# 2017-09-15_drum_circuits.net
KiCad netlist of a schematic drawn in EAGLE
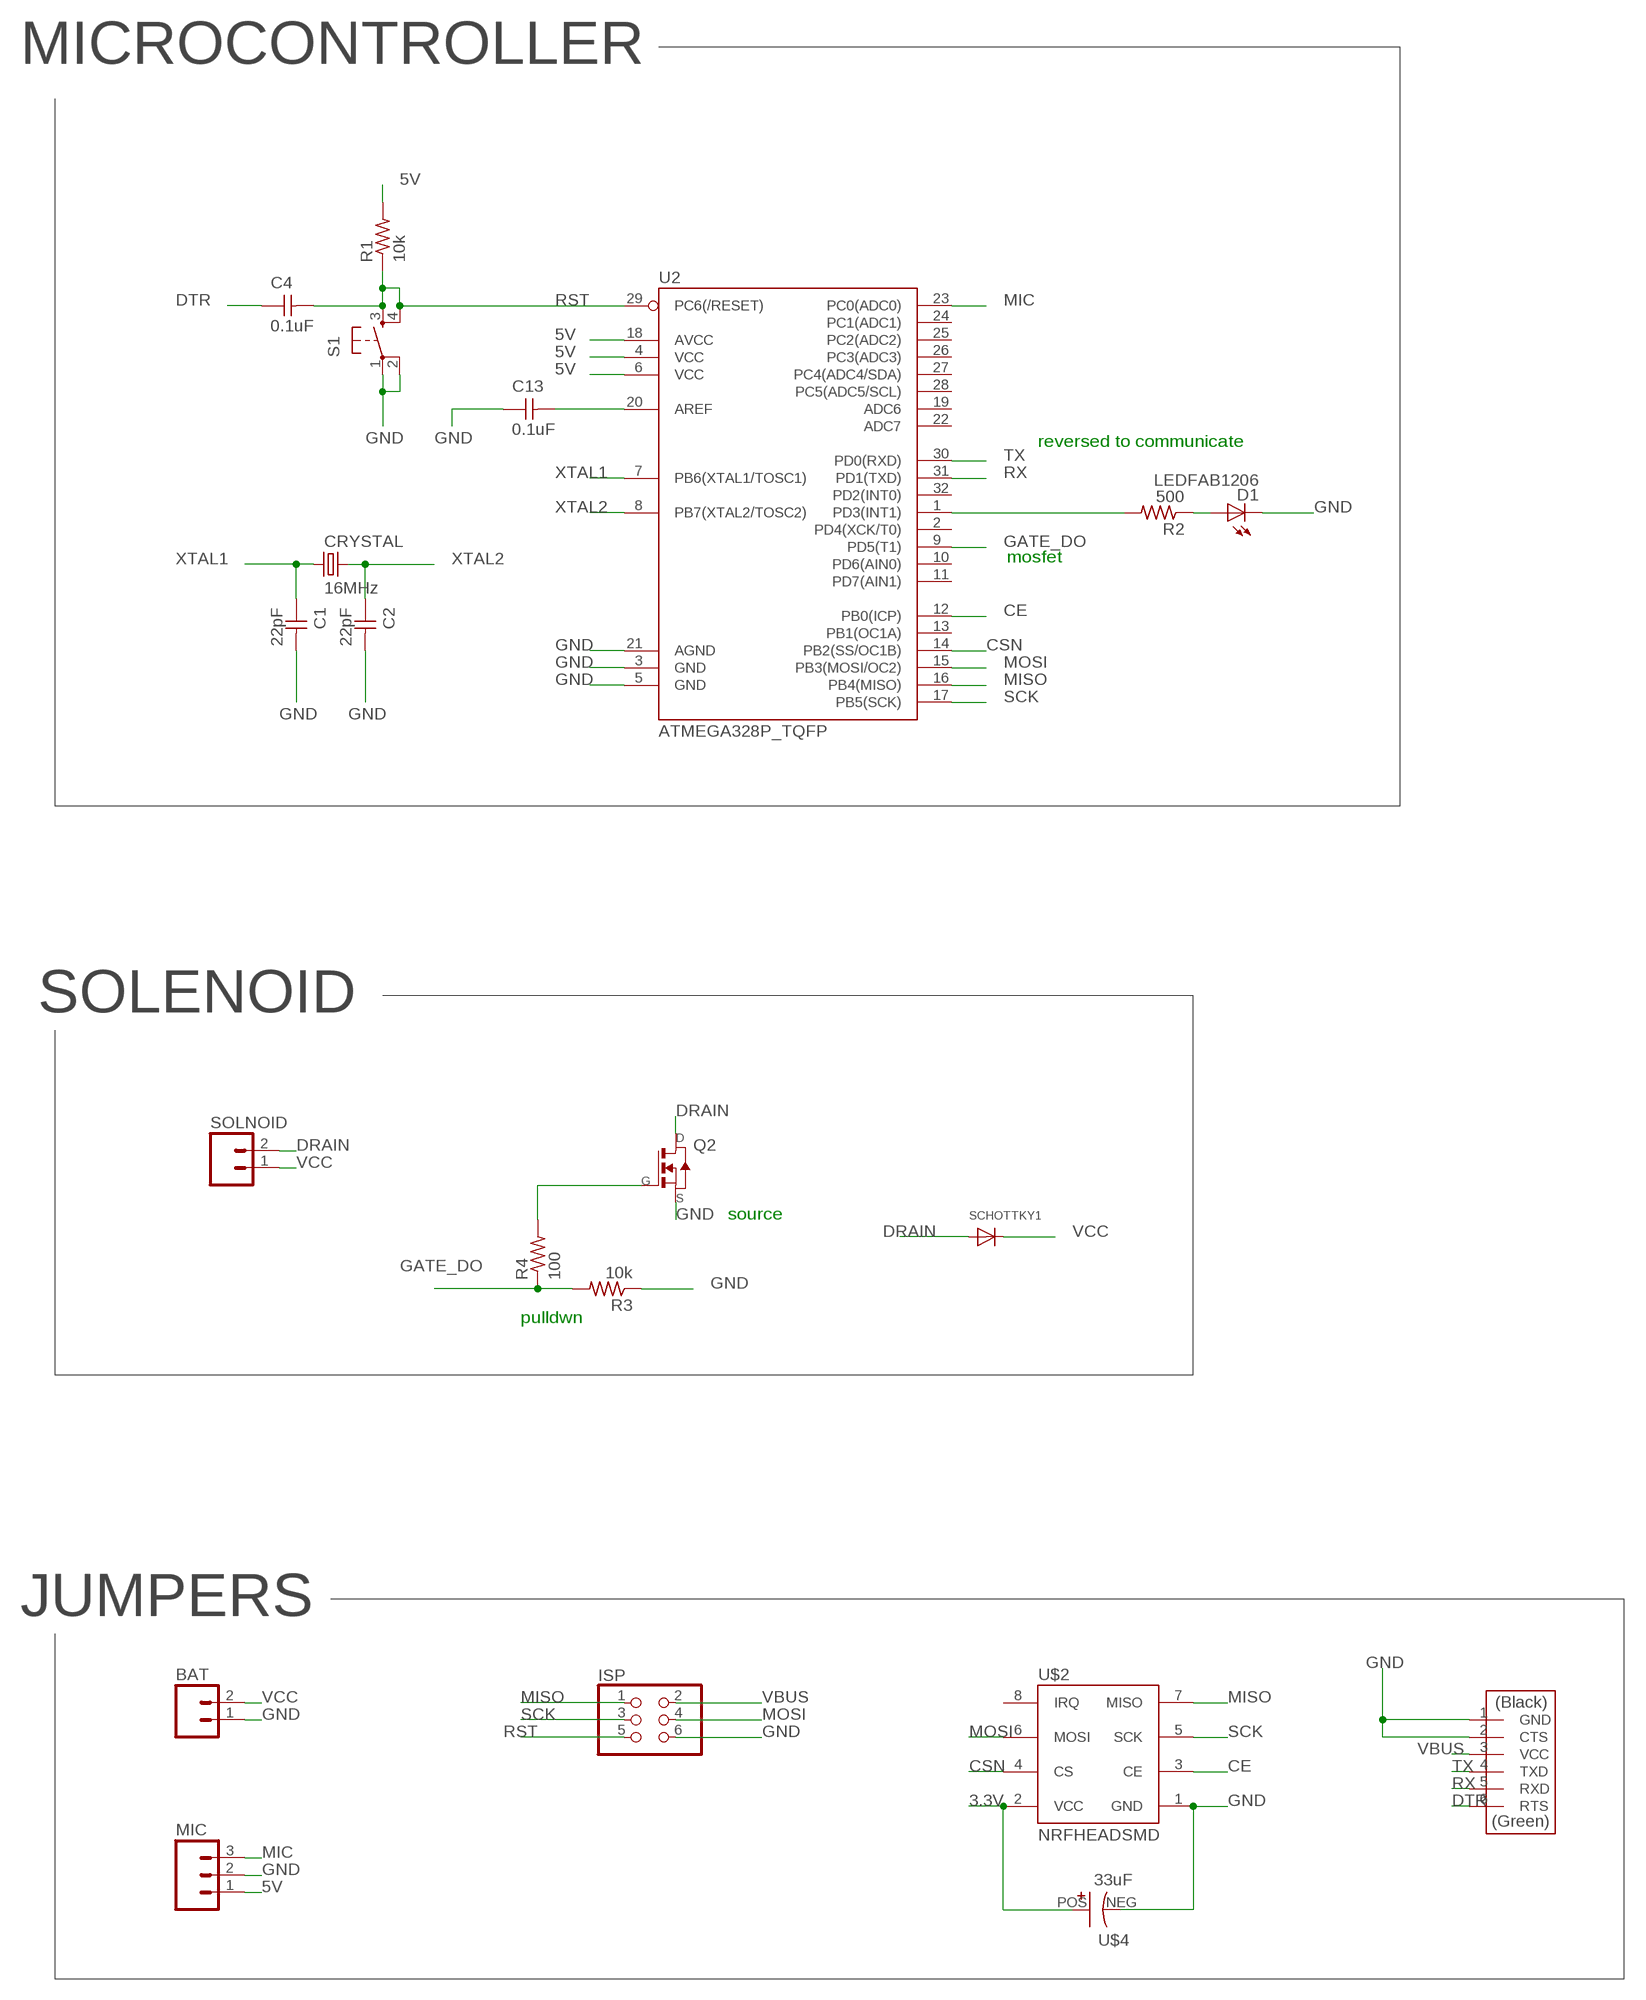
[diagram p0: schematic, sheet 1, part 1 of 2]
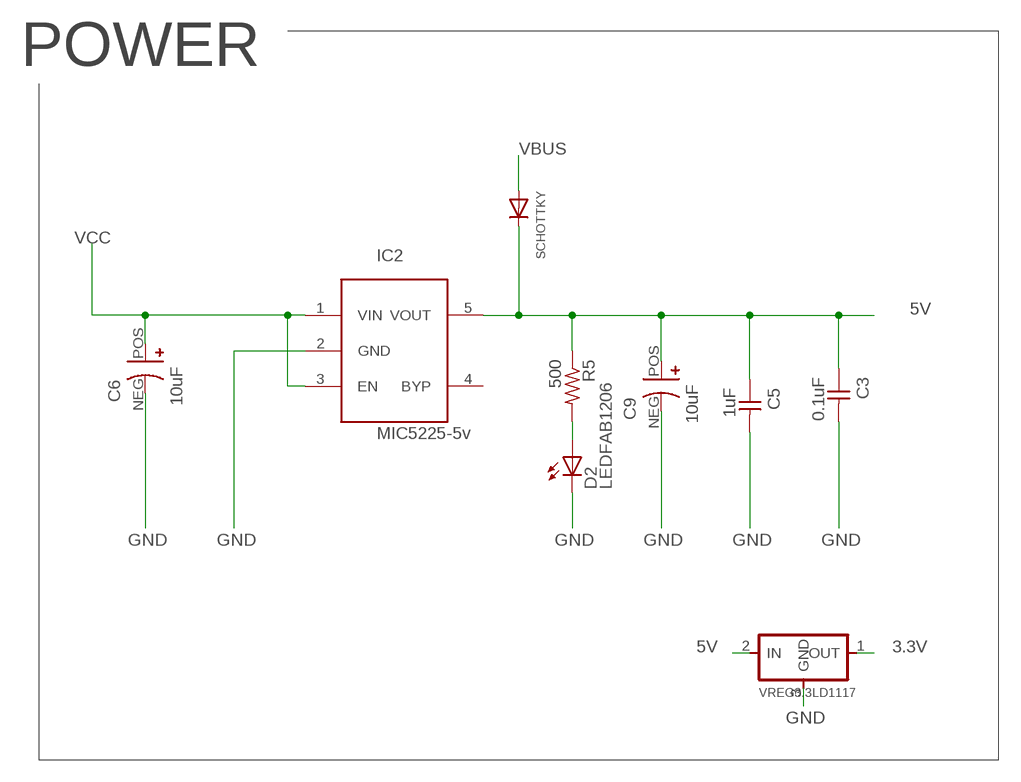
[diagram p1: schematic, sheet 1, part 2 of 2]

(export (version "E")
  (design (tool "Eeschema 10.0.6"))
  (components
    (comp (ref "BAT")
      (value "M02PTH")
      (footprint "eagle-import:1X02")
      (libsource (lib "eagle-import") (part "M02PTH"))
    )
    (comp (ref "C1")
      (value "22pF")
      (footprint "eagle-import:C1206FAB")
      (libsource (lib "eagle-import") (part "CAP-UNPOLARIZEDFAB"))
    )
    (comp (ref "C2")
      (value "22pF")
      (footprint "eagle-import:C1206FAB")
      (libsource (lib "eagle-import") (part "CAP-UNPOLARIZEDFAB"))
    )
    (comp (ref "C3")
      (value "0.1uF")
      (footprint "eagle-import:C1206FAB")
      (libsource (lib "eagle-import") (part "CAP-UNPOLARIZEDFAB"))
    )
    (comp (ref "C4")
      (value "0.1uF")
      (footprint "eagle-import:C1206FAB")
      (libsource (lib "eagle-import") (part "CAP-UNPOLARIZEDFAB"))
    )
    (comp (ref "C5")
      (value "1uF")
      (footprint "eagle-import:C1206FAB")
      (libsource (lib "eagle-import") (part "CAP-UNPOLARIZEDFAB"))
    )
    (comp (ref "C6")
      (value "10uF")
      (footprint "eagle-import:PANASONIC-CAP-SMD-B")
      (libsource (lib "eagle-import") (part "POLCAP-PANASONIC-SMD-B01"))
    )
    (comp (ref "C9")
      (value "10uF")
      (footprint "eagle-import:PANASONIC-CAP-SMD-B")
      (libsource (lib "eagle-import") (part "POLCAP-PANASONIC-SMD-B01"))
    )
    (comp (ref "C13")
      (value "0.1uF")
      (footprint "eagle-import:C1206FAB")
      (libsource (lib "eagle-import") (part "CAP-UNPOLARIZEDFAB"))
    )
    (comp (ref "CRYSTAL")
      (value "16MHz")
      (footprint "eagle-import:2-SMD-5X3MM")
      (libsource (lib "eagle-import") (part "CRYSTAL"))
    )
    (comp (ref "D1")
      (value "LEDFAB1206")
      (footprint "eagle-import:LED1206FAB")
      (libsource (lib "eagle-import") (part "LEDFAB1206"))
    )
    (comp (ref "D2")
      (value "LEDFAB1206")
      (footprint "eagle-import:LED1206FAB")
      (libsource (lib "eagle-import") (part "LEDFAB1206"))
    )
    (comp (ref "IC2")
      (value "MIC5225-5v")
      (footprint "eagle-import:SOT23-5L")
      (libsource (lib "eagle-import") (part "LP298XS"))
    )
    (comp (ref "ISP")
      (value "PINHD-2X3-SMD")
      (footprint "eagle-import:2X03SMD")
      (libsource (lib "eagle-import") (part "PINHD-2X3-SMD"))
    )
    (comp (ref "MIC")
      (value "M03PTH")
      (footprint "eagle-import:1X03")
      (libsource (lib "eagle-import") (part "M03PTH"))
    )
    (comp (ref "Q2")
      (value "NMOSFETSOT23")
      (footprint "eagle-import:SOT-23")
      (libsource (lib "eagle-import") (part "NMOSFETSOT23"))
    )
    (comp (ref "R1")
      (value "10k")
      (footprint "eagle-import:R1206FAB")
      (libsource (lib "eagle-import") (part "RES-US1206FAB"))
    )
    (comp (ref "R2")
      (value "500")
      (footprint "eagle-import:R1206FAB")
      (libsource (lib "eagle-import") (part "RES-US1206FAB"))
    )
    (comp (ref "R3")
      (value "10k")
      (footprint "eagle-import:R1206FAB")
      (libsource (lib "eagle-import") (part "RES-US1206FAB"))
    )
    (comp (ref "R4")
      (value "100")
      (footprint "eagle-import:R1206FAB")
      (libsource (lib "eagle-import") (part "RES-US1206FAB"))
    )
    (comp (ref "R5")
      (value "500")
      (footprint "eagle-import:R1206FAB")
      (libsource (lib "eagle-import") (part "RES-US1206FAB"))
    )
    (comp (ref "S1")
      (value "6MM_SWITCH6MM_SWITCH")
      (footprint "eagle-import:6MM_SWITCH")
      (libsource (lib "eagle-import") (part "6MM_SWITCH6MM_SWITCH"))
    )
    (comp (ref "SCHOTTKY")
      (value "DIODE_SOD-123FL")
      (footprint "eagle-import:SOD-123FL")
      (libsource (lib "eagle-import") (part "DIODE_SOD-123FL"))
    )
    (comp (ref "SCHOTTKY1")
      (value "DIODE_SOD-123FL")
      (footprint "eagle-import:SOD-123FL")
      (libsource (lib "eagle-import") (part "DIODE_SOD-123FL"))
    )
    (comp (ref "SOLNOID")
      (value "M02PTH")
      (footprint "eagle-import:1X02")
      (libsource (lib "eagle-import") (part "M02PTH"))
    )
    (comp (ref "U$1")
      (value "FTDI-SMD-HEADER")
      (footprint "eagle-import:1X06SMD")
      (libsource (lib "eagle-import") (part "FTDI-SMD-HEADER"))
    )
    (comp (ref "U$2")
      (value "NRFHEADSMD")
      (footprint "eagle-import:2.54MM")
      (libsource (lib "eagle-import") (part "NRFHEADSMD"))
    )
    (comp (ref "U$4")
      (value "33uF")
      (footprint "eagle-import:PANASONIC-CAP-SMD-C")
      (libsource (lib "eagle-import") (part "POLCAP-PANASONIC-SMD-C"))
    )
    (comp (ref "U2")
      (value "ATMEGA328P_TQFP")
      (footprint "eagle-import:TQFP32-08")
      (libsource (lib "eagle-import") (part "ATMEGA328P_TQFP"))
    )
    (comp (ref "VREG3.3")
      (value "LD1117")
      (footprint "eagle-import:SOT23")
      (libsource (lib "eagle-import") (part "REGULATORSOT23"))
    )
  )
  (nets
    (net (code "1") (name "/3.3V") (class "Default")
      (node (ref "U$2") (pin "2") (pinfunction "VCC_2") (pintype "bidirectional"))
      (node (ref "U$4") (pin "POS") (pinfunction "+_POS") (pintype "bidirectional"))
      (node (ref "VREG3.3") (pin "1") (pinfunction "OUT_1") (pintype "bidirectional"))
    )
    (net (code "2") (name "/5V") (class "Default")
      (node (ref "C3") (pin "1") (pinfunction "1_1") (pintype "passive"))
      (node (ref "C5") (pin "1") (pinfunction "1_1") (pintype "passive"))
      (node (ref "C9") (pin "POS") (pinfunction "+_POS") (pintype "bidirectional"))
      (node (ref "IC2") (pin "5") (pinfunction "VOUT_5") (pintype "bidirectional"))
      (node (ref "MIC") (pin "1") (pinfunction "1_1") (pintype "passive"))
      (node (ref "R1") (pin "2") (pinfunction "2_2") (pintype "passive"))
      (node (ref "R5") (pin "1") (pinfunction "1_1") (pintype "passive"))
      (node (ref "SCHOTTKY") (pin "C") (pinfunction "C_C") (pintype "passive"))
      (node (ref "U2") (pin "18") (pinfunction "AVCC_18") (pintype "bidirectional"))
      (node (ref "U2") (pin "4") (pinfunction "VCC_4") (pintype "bidirectional"))
      (node (ref "U2") (pin "6") (pinfunction "VCC_6") (pintype "bidirectional"))
      (node (ref "VREG3.3") (pin "2") (pinfunction "IN_2") (pintype "bidirectional"))
    )
    (net (code "3") (name "/CE") (class "Default")
      (node (ref "U$2") (pin "3") (pinfunction "CE_3") (pintype "bidirectional"))
      (node (ref "U2") (pin "12") (pinfunction "PB0(ICP)_12") (pintype "bidirectional"))
    )
    (net (code "4") (name "/CSN") (class "Default")
      (node (ref "U$2") (pin "4") (pinfunction "CS_4") (pintype "bidirectional"))
      (node (ref "U2") (pin "14") (pinfunction "PB2(SS/OC1B)_14") (pintype "bidirectional"))
    )
    (net (code "5") (name "/DRAIN") (class "Default")
      (node (ref "Q2") (pin "1") (pinfunction "D_1") (pintype "passive"))
      (node (ref "SCHOTTKY1") (pin "A") (pinfunction "A_A") (pintype "passive"))
      (node (ref "SOLNOID") (pin "2") (pinfunction "2_2") (pintype "passive"))
    )
    (net (code "6") (name "/DTR") (class "Default")
      (node (ref "C4") (pin "1") (pinfunction "1_1") (pintype "passive"))
      (node (ref "U$1") (pin "6") (pinfunction "RTS_6") (pintype "bidirectional"))
    )
    (net (code "7") (name "/GATE_DO") (class "Default")
      (node (ref "R3") (pin "2") (pinfunction "2_2") (pintype "passive"))
      (node (ref "R4") (pin "1") (pinfunction "1_1") (pintype "passive"))
      (node (ref "U2") (pin "9") (pinfunction "PD5(T1)_9") (pintype "bidirectional"))
    )
    (net (code "8") (name "/GND") (class "Default")
      (node (ref "BAT") (pin "1") (pinfunction "1_1") (pintype "passive"))
      (node (ref "C1") (pin "2") (pinfunction "2_2") (pintype "passive"))
      (node (ref "C13") (pin "1") (pinfunction "1_1") (pintype "passive"))
      (node (ref "C2") (pin "2") (pinfunction "2_2") (pintype "passive"))
      (node (ref "C3") (pin "2") (pinfunction "2_2") (pintype "passive"))
      (node (ref "C5") (pin "2") (pinfunction "2_2") (pintype "passive"))
      (node (ref "C6") (pin "NEG") (pinfunction "-_NEG") (pintype "bidirectional"))
      (node (ref "C9") (pin "NEG") (pinfunction "-_NEG") (pintype "bidirectional"))
      (node (ref "D1") (pin "2") (pinfunction "C_2") (pintype "passive"))
      (node (ref "D2") (pin "2") (pinfunction "C_2") (pintype "passive"))
      (node (ref "IC2") (pin "2") (pinfunction "GND_2") (pintype "bidirectional"))
      (node (ref "ISP") (pin "6") (pinfunction "6_6") (pintype "passive"))
      (node (ref "MIC") (pin "2") (pinfunction "2_2") (pintype "passive"))
      (node (ref "Q2") (pin "2") (pinfunction "S_2") (pintype "passive"))
      (node (ref "R3") (pin "1") (pinfunction "1_1") (pintype "passive"))
      (node (ref "S1") (pin "1") (pinfunction "P_1") (pintype "passive"))
      (node (ref "S1") (pin "2") (pinfunction "P1_2") (pintype "passive"))
      (node (ref "U$1") (pin "1") (pinfunction "GND_1") (pintype "bidirectional"))
      (node (ref "U$1") (pin "2") (pinfunction "CTS_2") (pintype "bidirectional"))
      (node (ref "U$2") (pin "1") (pinfunction "GND_1") (pintype "bidirectional"))
      (node (ref "U$4") (pin "NEG") (pinfunction "-_NEG") (pintype "bidirectional"))
      (node (ref "U2") (pin "21") (pinfunction "AGND_21") (pintype "bidirectional"))
      (node (ref "U2") (pin "3") (pinfunction "GND_3") (pintype "bidirectional"))
      (node (ref "U2") (pin "5") (pinfunction "GND_5") (pintype "bidirectional"))
      (node (ref "VREG3.3") (pin "3") (pinfunction "GND_3") (pintype "bidirectional"))
    )
    (net (code "9") (name "/MIC") (class "Default")
      (node (ref "MIC") (pin "3") (pinfunction "3_3") (pintype "passive"))
      (node (ref "U2") (pin "23") (pinfunction "PC0(ADC0)_23") (pintype "bidirectional"))
    )
    (net (code "10") (name "/MISO") (class "Default")
      (node (ref "ISP") (pin "1") (pinfunction "1_1") (pintype "passive"))
      (node (ref "U$2") (pin "7") (pinfunction "MISO_7") (pintype "bidirectional"))
      (node (ref "U2") (pin "16") (pinfunction "PB4(MISO)_16") (pintype "bidirectional"))
    )
    (net (code "11") (name "/MOSI") (class "Default")
      (node (ref "ISP") (pin "4") (pinfunction "4_4") (pintype "passive"))
      (node (ref "U$2") (pin "6") (pinfunction "MOSI_6") (pintype "bidirectional"))
      (node (ref "U2") (pin "15") (pinfunction "PB3(MOSI/OC2)_15") (pintype "bidirectional"))
    )
    (net (code "12") (name "/RST") (class "Default")
      (node (ref "C4") (pin "2") (pinfunction "2_2") (pintype "passive"))
      (node (ref "ISP") (pin "5") (pinfunction "5_5") (pintype "passive"))
      (node (ref "R1") (pin "1") (pinfunction "1_1") (pintype "passive"))
      (node (ref "S1") (pin "3") (pinfunction "S_3") (pintype "passive"))
      (node (ref "S1") (pin "4") (pinfunction "S1_4") (pintype "passive"))
      (node (ref "U2") (pin "29") (pinfunction "PC6(/RESET)_29") (pintype "bidirectional"))
    )
    (net (code "13") (name "/RX") (class "Default")
      (node (ref "U$1") (pin "5") (pinfunction "RXD_5") (pintype "bidirectional"))
      (node (ref "U2") (pin "31") (pinfunction "PD1(TXD)_31") (pintype "bidirectional"))
    )
    (net (code "14") (name "/SCK") (class "Default")
      (node (ref "ISP") (pin "3") (pinfunction "3_3") (pintype "passive"))
      (node (ref "U$2") (pin "5") (pinfunction "SCK_5") (pintype "bidirectional"))
      (node (ref "U2") (pin "17") (pinfunction "PB5(SCK)_17") (pintype "bidirectional"))
    )
    (net (code "15") (name "/TX") (class "Default")
      (node (ref "U$1") (pin "4") (pinfunction "TXD_4") (pintype "bidirectional"))
      (node (ref "U2") (pin "30") (pinfunction "PD0(RXD)_30") (pintype "bidirectional"))
    )
    (net (code "16") (name "/VBUS") (class "Default")
      (node (ref "ISP") (pin "2") (pinfunction "2_2") (pintype "passive"))
      (node (ref "SCHOTTKY") (pin "A") (pinfunction "A_A") (pintype "passive"))
      (node (ref "U$1") (pin "3") (pinfunction "VCC_3") (pintype "bidirectional"))
    )
    (net (code "17") (name "/VCC") (class "Default")
      (node (ref "BAT") (pin "2") (pinfunction "2_2") (pintype "passive"))
      (node (ref "C6") (pin "POS") (pinfunction "+_POS") (pintype "bidirectional"))
      (node (ref "IC2") (pin "1") (pinfunction "VIN_1") (pintype "bidirectional"))
      (node (ref "IC2") (pin "3") (pinfunction "EN_3") (pintype "bidirectional"))
      (node (ref "SCHOTTKY1") (pin "C") (pinfunction "C_C") (pintype "passive"))
      (node (ref "SOLNOID") (pin "1") (pinfunction "1_1") (pintype "passive"))
    )
    (net (code "18") (name "/XTAL1") (class "Default")
      (node (ref "C1") (pin "1") (pinfunction "1_1") (pintype "passive"))
      (node (ref "CRYSTAL") (pin "P$1") (pinfunction "1_P$1") (pintype "passive"))
      (node (ref "U2") (pin "7") (pinfunction "PB6(XTAL1/TOSC1)_7") (pintype "bidirectional"))
    )
    (net (code "19") (name "/XTAL2") (class "Default")
      (node (ref "C2") (pin "1") (pinfunction "1_1") (pintype "passive"))
      (node (ref "CRYSTAL") (pin "P$2") (pinfunction "2_P$2") (pintype "passive"))
      (node (ref "U2") (pin "8") (pinfunction "PB7(XTAL2/TOSC2)_8") (pintype "bidirectional"))
    )
    (net (code "20") (name "Net-(D1-A)") (class "Default")
      (node (ref "D1") (pin "1") (pinfunction "A_1") (pintype "passive"))
      (node (ref "R2") (pin "1") (pinfunction "1_1") (pintype "passive"))
    )
    (net (code "21") (name "Net-(D2-A)") (class "Default")
      (node (ref "D2") (pin "1") (pinfunction "A_1") (pintype "passive"))
      (node (ref "R5") (pin "2") (pinfunction "2_2") (pintype "passive"))
    )
    (net (code "22") (name "Net-(Q2-G)") (class "Default")
      (node (ref "Q2") (pin "3") (pinfunction "G_3") (pintype "passive"))
      (node (ref "R4") (pin "2") (pinfunction "2_2") (pintype "passive"))
    )
    (net (code "23") (name "Net-(U2-AREF)") (class "Default")
      (node (ref "C13") (pin "2") (pinfunction "2_2") (pintype "passive"))
      (node (ref "U2") (pin "20") (pinfunction "AREF_20") (pintype "bidirectional"))
    )
    (net (code "24") (name "Net-(U2-PD3(INT1))") (class "Default")
      (node (ref "R2") (pin "2") (pinfunction "2_2") (pintype "passive"))
      (node (ref "U2") (pin "1") (pinfunction "PD3(INT1)_1") (pintype "bidirectional"))
    )
    (net (code "25") (name "unconnected-(IC2-BYP-Pad4)") (class "Default")
      (node (ref "IC2") (pin "4") (pinfunction "BYP_4") (pintype "bidirectional"))
    )
    (net (code "26") (name "unconnected-(U$2-IRQ-Pad8)") (class "Default")
      (node (ref "U$2") (pin "8") (pinfunction "IRQ_8") (pintype "bidirectional"))
    )
    (net (code "27") (name "unconnected-(U2-ADC6-Pad19)") (class "Default")
      (node (ref "U2") (pin "19") (pinfunction "ADC6_19") (pintype "bidirectional"))
    )
    (net (code "28") (name "unconnected-(U2-ADC7-Pad22)") (class "Default")
      (node (ref "U2") (pin "22") (pinfunction "ADC7_22") (pintype "bidirectional"))
    )
    (net (code "29") (name "unconnected-(U2-PB1(OC1A)-Pad13)") (class "Default")
      (node (ref "U2") (pin "13") (pinfunction "PB1(OC1A)_13") (pintype "bidirectional"))
    )
    (net (code "30") (name "unconnected-(U2-PC1(ADC1)-Pad24)") (class "Default")
      (node (ref "U2") (pin "24") (pinfunction "PC1(ADC1)_24") (pintype "bidirectional"))
    )
    (net (code "31") (name "unconnected-(U2-PC2(ADC2)-Pad25)") (class "Default")
      (node (ref "U2") (pin "25") (pinfunction "PC2(ADC2)_25") (pintype "bidirectional"))
    )
    (net (code "32") (name "unconnected-(U2-PC3(ADC3)-Pad26)") (class "Default")
      (node (ref "U2") (pin "26") (pinfunction "PC3(ADC3)_26") (pintype "bidirectional"))
    )
    (net (code "33") (name "unconnected-(U2-PC4(ADC4{slash}SDA)-Pad27)") (class "Default")
      (node (ref "U2") (pin "27") (pinfunction "PC4(ADC4/SDA)_27") (pintype "bidirectional"))
    )
    (net (code "34") (name "unconnected-(U2-PC5(ADC5{slash}SCL)-Pad28)") (class "Default")
      (node (ref "U2") (pin "28") (pinfunction "PC5(ADC5/SCL)_28") (pintype "bidirectional"))
    )
    (net (code "35") (name "unconnected-(U2-PD2(INT0)-Pad32)") (class "Default")
      (node (ref "U2") (pin "32") (pinfunction "PD2(INT0)_32") (pintype "bidirectional"))
    )
    (net (code "36") (name "unconnected-(U2-PD4(XCK{slash}T0)-Pad2)") (class "Default")
      (node (ref "U2") (pin "2") (pinfunction "PD4(XCK/T0)_2") (pintype "bidirectional"))
    )
    (net (code "37") (name "unconnected-(U2-PD6(AIN0)-Pad10)") (class "Default")
      (node (ref "U2") (pin "10") (pinfunction "PD6(AIN0)_10") (pintype "bidirectional"))
    )
    (net (code "38") (name "unconnected-(U2-PD7(AIN1)-Pad11)") (class "Default")
      (node (ref "U2") (pin "11") (pinfunction "PD7(AIN1)_11") (pintype "bidirectional"))
    )
  )
)
